# ProPrj_F080104_2024-08-08.net
KiCad netlist of a schematic drawn in EasyEDA Pro
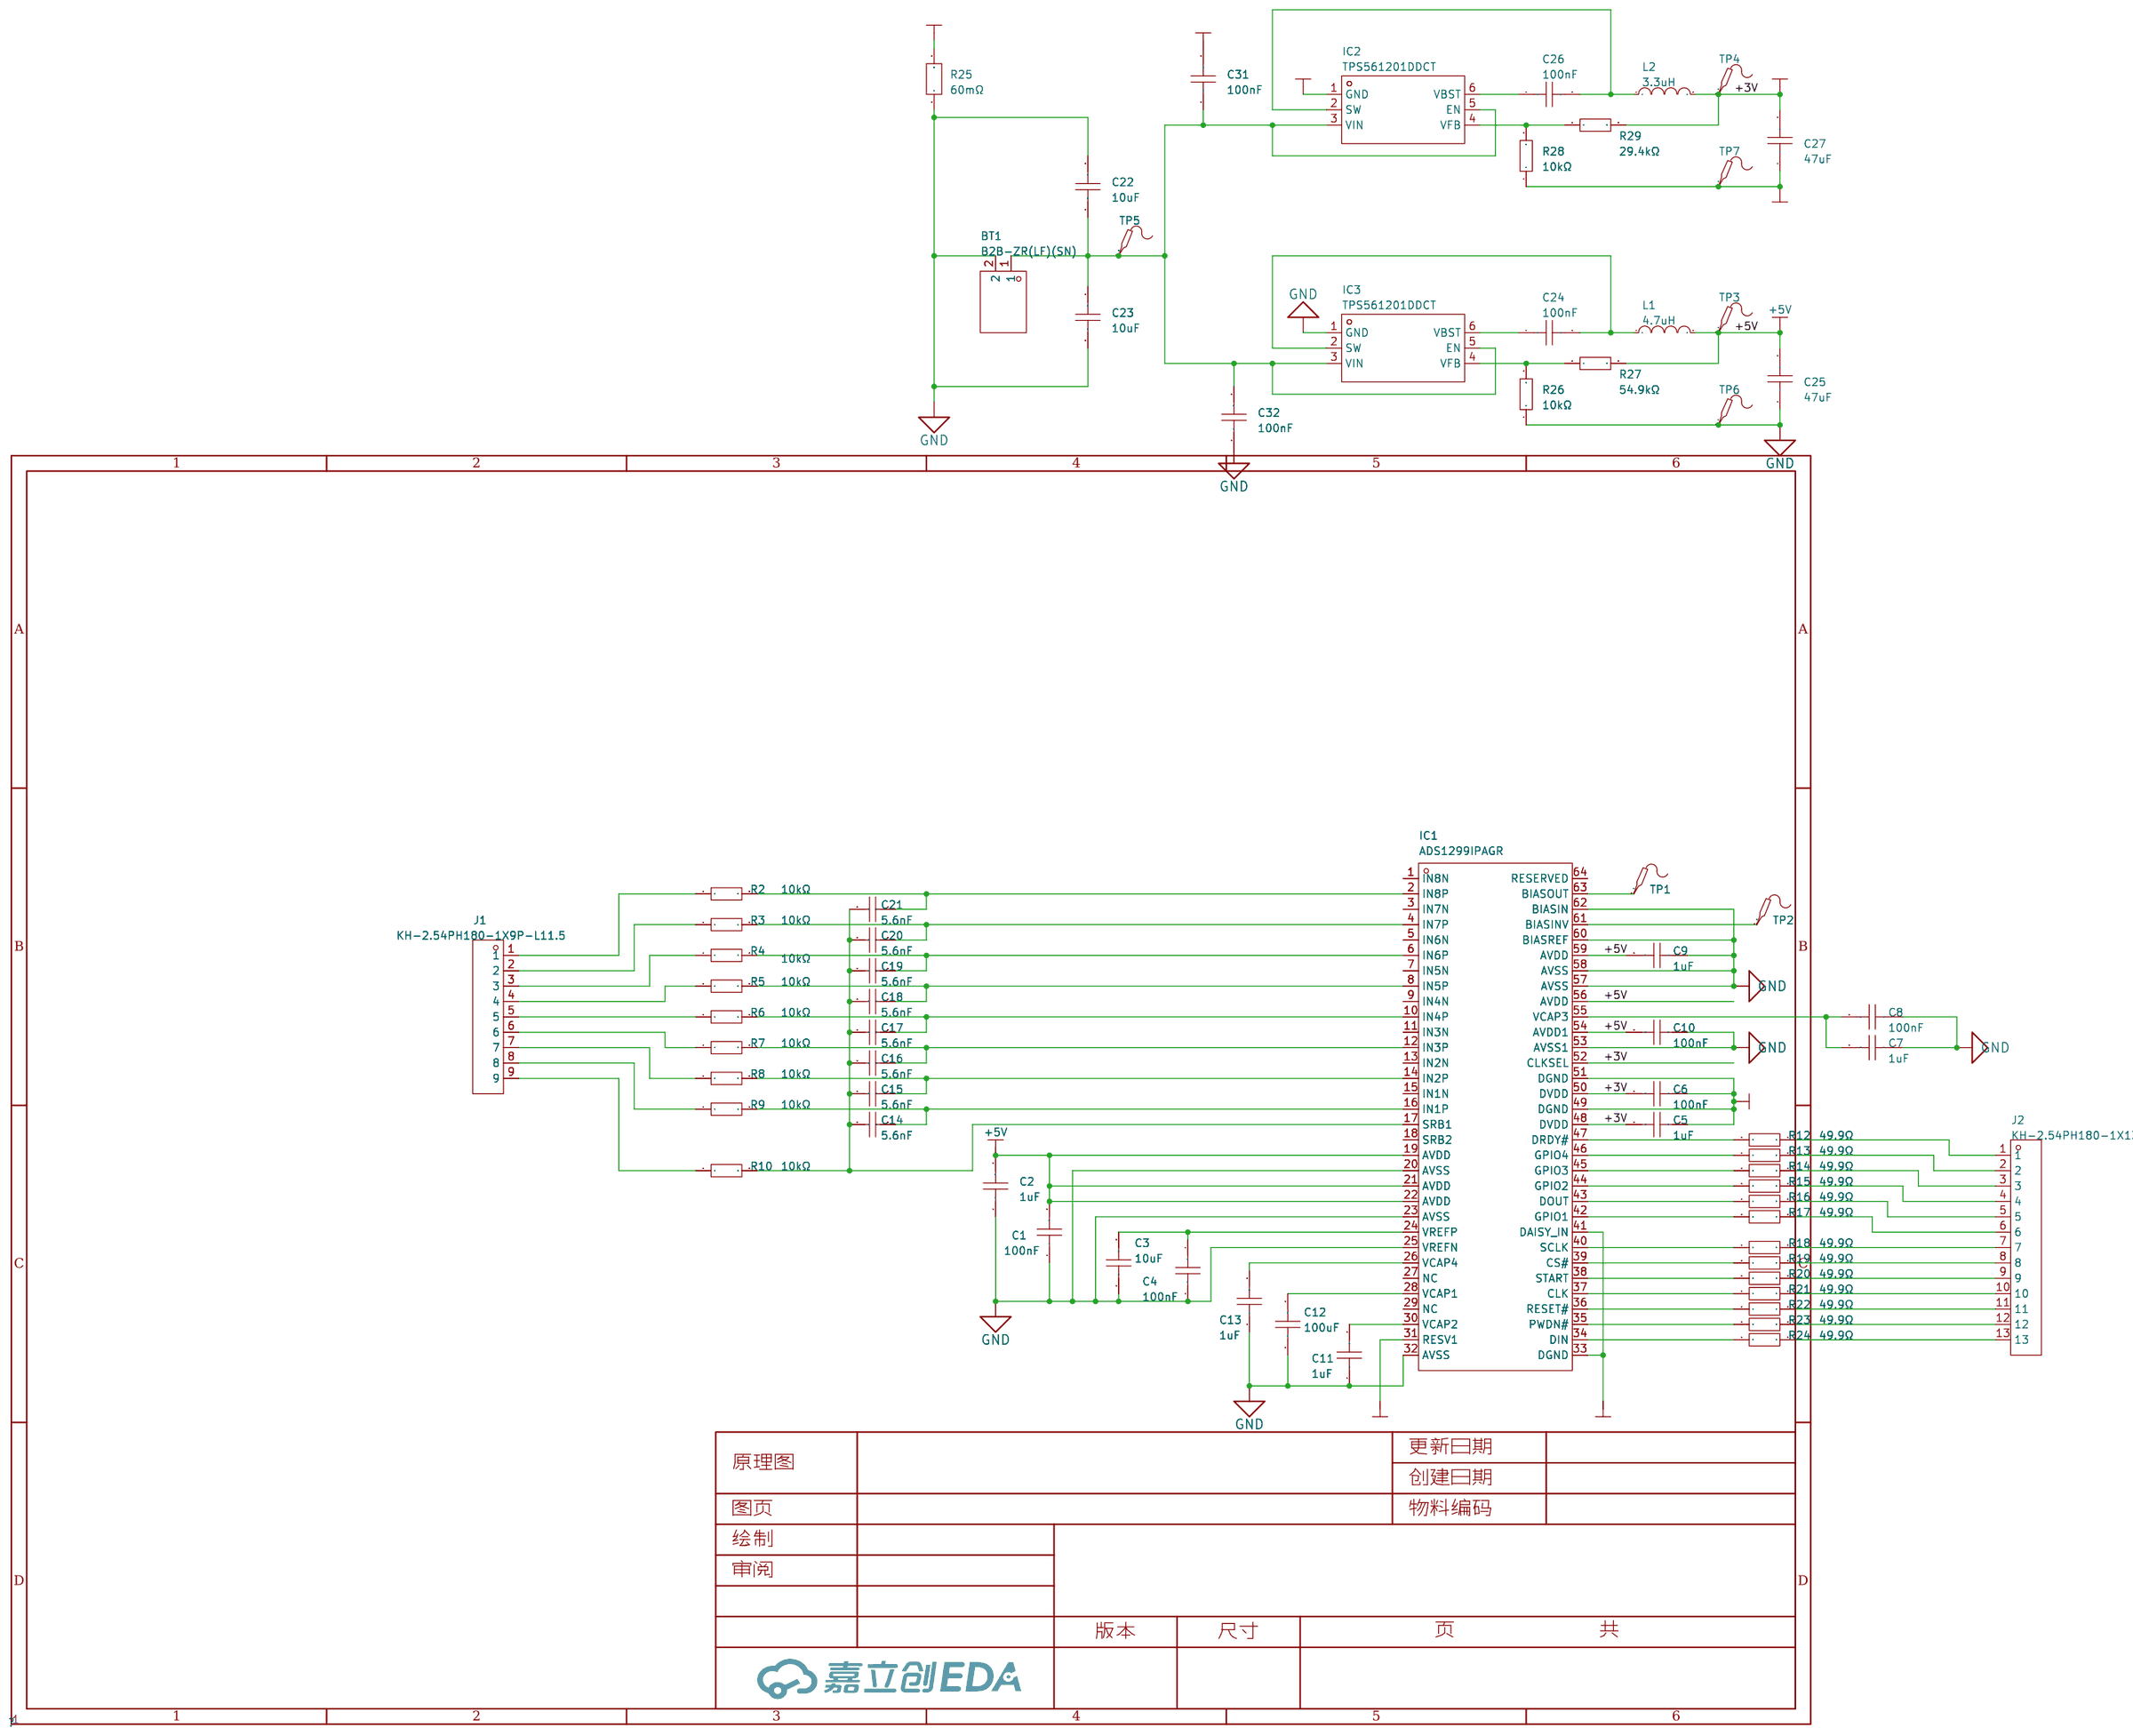
[diagram p0: schematic sheet]

(export (version "E")
  (design (tool "Eeschema 10.0.6"))
  (components
    (comp (ref "BT1")
      (value "B2B-ZR(LF)(SN)")
      (footprint "easyedapro:CONN-TH_B2B-ZR-LF-SN")
      (fields (field (name "Manufacturer") "JST"))
      (libsource (lib "easyedapro") (part "B2B-ZR (LF)(SN)"))
    )
    (comp (ref "C1")
      (value "100nF")
      (footprint "easyedapro:C0603")
      (description "容值:100nF;精度:±10%;额定电压:50V;材质(温度系数):X7R;")
      (fields
        (field (name "Manufacturer Part") "CC0603KRX7R9BB104")
        (field (name "Manufacturer") "YAGEO(国巨)")
      )
      (libsource (lib "easyedapro") (part "CC0603KRX7R9BB104"))
    )
    (comp (ref "C2")
      (value "1uF")
      (footprint "easyedapro:C0603")
      (description "容值:1uF;精度:±10%;额定电压:50V;材质(温度系数):X5R;")
      (fields
        (field (name "Manufacturer Part") "CL10A105KB8NNNC")
        (field (name "Manufacturer") "SAMSUNG(三星)")
      )
      (libsource (lib "easyedapro") (part "CL10A105KB8NNNC"))
    )
    (comp (ref "C3")
      (value "10uF")
      (footprint "easyedapro:C0805")
      (description "容值:10uF;精度:±10%;额定电压:25V;材质(温度系数):X5R;")
      (fields
        (field (name "Manufacturer Part") "CL21A106KAYNNNE")
        (field (name "Manufacturer") "SAMSUNG(三星)")
      )
      (libsource (lib "easyedapro") (part "CL21A106KAYNNNE"))
    )
    (comp (ref "C4")
      (value "100nF")
      (footprint "easyedapro:C0603")
      (description "容值:100nF;精度:±10%;额定电压:50V;材质(温度系数):X7R;")
      (fields
        (field (name "Manufacturer Part") "CC0603KRX7R9BB104")
        (field (name "Manufacturer") "YAGEO(国巨)")
      )
      (libsource (lib "easyedapro") (part "CC0603KRX7R9BB104"))
    )
    (comp (ref "C5")
      (value "1uF")
      (footprint "easyedapro:C0603")
      (description "容值:1uF;精度:±10%;额定电压:50V;材质(温度系数):X5R;")
      (fields
        (field (name "Manufacturer Part") "CL10A105KB8NNNC")
        (field (name "Manufacturer") "SAMSUNG(三星)")
      )
      (libsource (lib "easyedapro") (part "CL10A105KB8NNNC"))
    )
    (comp (ref "C6")
      (value "100nF")
      (footprint "easyedapro:C0603")
      (description "容值:100nF;精度:±10%;额定电压:50V;材质(温度系数):X7R;")
      (fields
        (field (name "Manufacturer Part") "CC0603KRX7R9BB104")
        (field (name "Manufacturer") "YAGEO(国巨)")
      )
      (libsource (lib "easyedapro") (part "CC0603KRX7R9BB104"))
    )
    (comp (ref "C7")
      (value "1uF")
      (footprint "easyedapro:C0603")
      (description "容值:1uF;精度:±10%;额定电压:50V;材质(温度系数):X5R;")
      (fields
        (field (name "Manufacturer Part") "CL10A105KB8NNNC")
        (field (name "Manufacturer") "SAMSUNG(三星)")
      )
      (libsource (lib "easyedapro") (part "CL10A105KB8NNNC"))
    )
    (comp (ref "C8")
      (value "100nF")
      (footprint "easyedapro:C0603")
      (description "容值:100nF;精度:±10%;额定电压:50V;材质(温度系数):X7R;")
      (fields
        (field (name "Manufacturer Part") "CC0603KRX7R9BB104")
        (field (name "Manufacturer") "YAGEO(国巨)")
      )
      (libsource (lib "easyedapro") (part "CC0603KRX7R9BB104"))
    )
    (comp (ref "C9")
      (value "1uF")
      (footprint "easyedapro:C0603")
      (description "容值:1uF;精度:±10%;额定电压:50V;材质(温度系数):X5R;")
      (fields
        (field (name "Manufacturer Part") "CL10A105KB8NNNC")
        (field (name "Manufacturer") "SAMSUNG(三星)")
      )
      (libsource (lib "easyedapro") (part "CL10A105KB8NNNC"))
    )
    (comp (ref "C10")
      (value "100nF")
      (footprint "easyedapro:C0603")
      (description "容值:100nF;精度:±10%;额定电压:50V;材质(温度系数):X7R;")
      (fields
        (field (name "Manufacturer Part") "CC0603KRX7R9BB104")
        (field (name "Manufacturer") "YAGEO(国巨)")
      )
      (libsource (lib "easyedapro") (part "CC0603KRX7R9BB104"))
    )
    (comp (ref "C11")
      (value "1uF")
      (footprint "easyedapro:C0603")
      (description "容值:1uF;精度:±10%;额定电压:50V;材质(温度系数):X5R;")
      (fields
        (field (name "Manufacturer Part") "CL10A105KB8NNNC")
        (field (name "Manufacturer") "SAMSUNG(三星)")
      )
      (libsource (lib "easyedapro") (part "CL10A105KB8NNNC"))
    )
    (comp (ref "C12")
      (value "100uF")
      (footprint "easyedapro:C1206")
      (description "容值:100uF;精度:±20%;额定电压:10V;材质(温度系数):X5R;")
      (fields
        (field (name "Manufacturer Part") "GRM31CR61A107ME05L")
        (field (name "Manufacturer") "muRata(村田)")
      )
      (libsource (lib "easyedapro") (part "GRM31CR61A107ME05L"))
    )
    (comp (ref "C13")
      (value "1uF")
      (footprint "easyedapro:C0603")
      (description "容值:1uF;精度:±10%;额定电压:50V;材质(温度系数):X5R;")
      (fields
        (field (name "Manufacturer Part") "CL10A105KB8NNNC")
        (field (name "Manufacturer") "SAMSUNG(三星)")
      )
      (libsource (lib "easyedapro") (part "CL10A105KB8NNNC"))
    )
    (comp (ref "C14")
      (value "5.6nF")
      (footprint "easyedapro:C0603")
      (description "容值:3.9nF;精度:±10%;额定电压:50V;材质(温度系数):X7R;")
      (fields
        (field (name "Manufacturer Part") "CC0603KRX7R9BB562")
        (field (name "Manufacturer") "YAGEO(国巨)")
      )
      (libsource (lib "easyedapro") (part "0603B392K500NT"))
    )
    (comp (ref "C15")
      (value "5.6nF")
      (footprint "easyedapro:C0603")
      (description "容值:3.9nF;精度:±10%;额定电压:50V;材质(温度系数):X7R;")
      (fields
        (field (name "Manufacturer Part") "CC0603KRX7R9BB562")
        (field (name "Manufacturer") "YAGEO(国巨)")
      )
      (libsource (lib "easyedapro") (part "0603B392K500NT"))
    )
    (comp (ref "C16")
      (value "5.6nF")
      (footprint "easyedapro:C0603")
      (description "容值:3.9nF;精度:±10%;额定电压:50V;材质(温度系数):X7R;")
      (fields
        (field (name "Manufacturer Part") "CC0603KRX7R9BB562")
        (field (name "Manufacturer") "YAGEO(国巨)")
      )
      (libsource (lib "easyedapro") (part "0603B392K500NT"))
    )
    (comp (ref "C17")
      (value "5.6nF")
      (footprint "easyedapro:C0603")
      (description "容值:3.9nF;精度:±10%;额定电压:50V;材质(温度系数):X7R;")
      (fields
        (field (name "Manufacturer Part") "CC0603KRX7R9BB562")
        (field (name "Manufacturer") "YAGEO(国巨)")
      )
      (libsource (lib "easyedapro") (part "0603B392K500NT"))
    )
    (comp (ref "C18")
      (value "5.6nF")
      (footprint "easyedapro:C0603")
      (description "容值:3.9nF;精度:±10%;额定电压:50V;材质(温度系数):X7R;")
      (fields
        (field (name "Manufacturer Part") "CC0603KRX7R9BB562")
        (field (name "Manufacturer") "YAGEO(国巨)")
      )
      (libsource (lib "easyedapro") (part "0603B392K500NT"))
    )
    (comp (ref "C19")
      (value "5.6nF")
      (footprint "easyedapro:C0603")
      (description "容值:3.9nF;精度:±10%;额定电压:50V;材质(温度系数):X7R;")
      (fields
        (field (name "Manufacturer Part") "CC0603KRX7R9BB562")
        (field (name "Manufacturer") "YAGEO(国巨)")
      )
      (libsource (lib "easyedapro") (part "0603B392K500NT"))
    )
    (comp (ref "C20")
      (value "5.6nF")
      (footprint "easyedapro:C0603")
      (description "容值:3.9nF;精度:±10%;额定电压:50V;材质(温度系数):X7R;")
      (fields
        (field (name "Manufacturer Part") "CC0603KRX7R9BB562")
        (field (name "Manufacturer") "YAGEO(国巨)")
      )
      (libsource (lib "easyedapro") (part "0603B392K500NT"))
    )
    (comp (ref "C21")
      (value "5.6nF")
      (footprint "easyedapro:C0603")
      (description "容值:3.9nF;精度:±10%;额定电压:50V;材质(温度系数):X7R;")
      (fields
        (field (name "Manufacturer Part") "CC0603KRX7R9BB562")
        (field (name "Manufacturer") "YAGEO(国巨)")
      )
      (libsource (lib "easyedapro") (part "0603B392K500NT"))
    )
    (comp (ref "C22")
      (value "10uF")
      (footprint "easyedapro:C0805")
      (description "容值:10uF;精度:±10%;额定电压:25V;材质(温度系数):X5R;")
      (fields
        (field (name "Manufacturer Part") "CL21A106KAYNNNE")
        (field (name "Manufacturer") "SAMSUNG(三星)")
      )
      (libsource (lib "easyedapro") (part "CL21A106KAYNNNE"))
    )
    (comp (ref "C23")
      (value "10uF")
      (footprint "easyedapro:C0805")
      (description "容值:10uF;精度:±10%;额定电压:25V;材质(温度系数):X5R;")
      (fields
        (field (name "Manufacturer Part") "CL21A106KAYNNNE")
        (field (name "Manufacturer") "SAMSUNG(三星)")
      )
      (libsource (lib "easyedapro") (part "CL21A106KAYNNNE"))
    )
    (comp (ref "C24")
      (value "100nF")
      (footprint "easyedapro:C0603")
      (description "容值:100nF;精度:±10%;额定电压:50V;材质(温度系数):X7R;")
      (fields
        (field (name "Manufacturer Part") "CC0603KRX7R9BB104")
        (field (name "Manufacturer") "YAGEO(国巨)")
      )
      (libsource (lib "easyedapro") (part "CC0603KRX7R9BB104"))
    )
    (comp (ref "C25")
      (value "47uF")
      (footprint "easyedapro:C0805")
      (description "容值:47uF;精度:±20%;额定电压:10V;材质(温度系数):X5R;")
      (fields
        (field (name "Manufacturer Part") "GRM21BR61A476ME15L")
        (field (name "Manufacturer") "muRata(村田)")
      )
      (libsource (lib "easyedapro") (part "GRM21BR61A476ME15L"))
    )
    (comp (ref "C26")
      (value "100nF")
      (footprint "easyedapro:C0603")
      (description "容值:100nF;精度:±10%;额定电压:50V;材质(温度系数):X7R;")
      (fields
        (field (name "Manufacturer Part") "CC0603KRX7R9BB104")
        (field (name "Manufacturer") "YAGEO(国巨)")
      )
      (libsource (lib "easyedapro") (part "CC0603KRX7R9BB104"))
    )
    (comp (ref "C27")
      (value "47uF")
      (footprint "easyedapro:C0805")
      (description "容值:47uF;精度:±20%;额定电压:10V;材质(温度系数):X5R;")
      (fields
        (field (name "Manufacturer Part") "GRM21BR61A476ME15L")
        (field (name "Manufacturer") "muRata(村田)")
      )
      (libsource (lib "easyedapro") (part "GRM21BR61A476ME15L"))
    )
    (comp (ref "C31")
      (value "100nF")
      (footprint "easyedapro:C0603")
      (description "容值:100nF;精度:±10%;额定电压:50V;材质(温度系数):X7R;")
      (fields
        (field (name "Manufacturer Part") "CC0603KRX7R9BB104")
        (field (name "Manufacturer") "YAGEO(国巨)")
      )
      (libsource (lib "easyedapro") (part "CC0603KRX7R9BB104"))
    )
    (comp (ref "C32")
      (value "100nF")
      (footprint "easyedapro:C0603")
      (description "容值:100nF;精度:±10%;额定电压:50V;材质(温度系数):X7R;")
      (fields
        (field (name "Manufacturer Part") "CC0603KRX7R9BB104")
        (field (name "Manufacturer") "YAGEO(国巨)")
      )
      (libsource (lib "easyedapro") (part "CC0603KRX7R9BB104"))
    )
    (comp (ref "IC1")
      (value "ADS1299IPAGR")
      (footprint "easyedapro:TQFP-64_L10.0-W10.0-P0.50-LS12.0-TL")
      (description "电源电压:5V；1.8V~3.6V;")
      (fields (field (name "Manufacturer") "TI(德州仪器)"))
      (libsource (lib "easyedapro") (part "ADS1299IPAGR"))
    )
    (comp (ref "IC2")
      (value "TPS561201DDCT")
      (footprint "easyedapro:SOT-23-6_L2.9-W1.6-P0.95-LS2.8-BR")
      (description "功能类型:降压型;输出类型:可调;输入电压:4.5V~17V;输出电压:760mV~7V;输出电流(最大值):1A;")
      (fields (field (name "Manufacturer") "TI(德州仪器)"))
      (libsource (lib "easyedapro") (part "TPS561201DDCT"))
    )
    (comp (ref "IC3")
      (value "TPS561201DDCT")
      (footprint "easyedapro:SOT-23-6_L2.9-W1.6-P0.95-LS2.8-BR")
      (description "功能类型:降压型;输出类型:可调;输入电压:4.5V~17V;输出电压:760mV~7V;输出电流(最大值):1A;")
      (fields (field (name "Manufacturer") "TI(德州仪器)"))
      (libsource (lib "easyedapro") (part "TPS561201DDCT"))
    )
    (comp (ref "J1")
      (value "KH-2.54PH180-1X9P-L11.5")
      (footprint "easyedapro:HDR-TH_9P-P2.54-V-M")
      (fields (field (name "Manufacturer") "kinghelm(金航标)"))
      (libsource (lib "easyedapro") (part "KH-2.54PH180-1X9P-L11.5"))
    )
    (comp (ref "J2")
      (value "KH-2.54PH180-1X13P-L11.5")
      (footprint "easyedapro:HDR-TH_13P-P2.54-V-M")
      (fields (field (name "Manufacturer") "kinghelm(金航标)"))
      (libsource (lib "easyedapro") (part "KH-2.54PH180-1X13P-L11.5"))
    )
    (comp (ref "L1")
      (value "4.7uH")
      (footprint "easyedapro:IND-SMD_L4.4-W4.2")
      (description "电感值:4.7uH;精度:±20%;额定电流:2.8A;饱和电流(Isat):3A;类型:一体成型电感;")
      (fields (field (name "Manufacturer Part") "FXL0420-4R7-M") (field (name "Manufacturer") "cjiang(长江微电)"))
      (libsource (lib "easyedapro") (part "FXL0420-4R7-M"))
    )
    (comp (ref "L2")
      (value "3.3uH")
      (footprint "easyedapro:IND-SMD_L4.4-W4.2-A")
      (description "电感值:3.3uH;精度:±20%;额定电流:3.3A;饱和电流(Isat):4A;类型:一体成型电感;")
      (fields (field (name "Manufacturer Part") "FXL0420-3R3-M") (field (name "Manufacturer") "cjiang(长江微电)"))
      (libsource (lib "easyedapro") (part "FXL0420-3R3-M"))
    )
    (comp (ref "R2")
      (value "10kΩ")
      (footprint "easyedapro:R0603")
      (description "电阻类型:厚膜电阻;阻值:10kΩ;精度:±1%;功率:100mW;最大工作电压:75V;温度系数:±100ppm/°C;")
      (fields
        (field (name "Manufacturer Part") "0603WAF1002T5E")
        (field (name "Manufacturer") "UNI-ROYAL(厚声)")
      )
      (libsource (lib "easyedapro") (part "0603WAF1002T5E"))
    )
    (comp (ref "R3")
      (value "10kΩ")
      (footprint "easyedapro:R0603")
      (description "电阻类型:厚膜电阻;阻值:10kΩ;精度:±1%;功率:100mW;最大工作电压:75V;温度系数:±100ppm/°C;")
      (fields
        (field (name "Manufacturer Part") "0603WAF1002T5E")
        (field (name "Manufacturer") "UNI-ROYAL(厚声)")
      )
      (libsource (lib "easyedapro") (part "0603WAF1002T5E"))
    )
    (comp (ref "R4")
      (value "10kΩ")
      (footprint "easyedapro:R0603")
      (description "电阻类型:厚膜电阻;阻值:10kΩ;精度:±1%;功率:100mW;最大工作电压:75V;温度系数:±100ppm/°C;")
      (fields
        (field (name "Manufacturer Part") "0603WAF1002T5E")
        (field (name "Manufacturer") "UNI-ROYAL(厚声)")
      )
      (libsource (lib "easyedapro") (part "0603WAF1002T5E"))
    )
    (comp (ref "R5")
      (value "10kΩ")
      (footprint "easyedapro:R0603")
      (description "电阻类型:厚膜电阻;阻值:10kΩ;精度:±1%;功率:100mW;最大工作电压:75V;温度系数:±100ppm/°C;")
      (fields
        (field (name "Manufacturer Part") "0603WAF1002T5E")
        (field (name "Manufacturer") "UNI-ROYAL(厚声)")
      )
      (libsource (lib "easyedapro") (part "0603WAF1002T5E"))
    )
    (comp (ref "R6")
      (value "10kΩ")
      (footprint "easyedapro:R0603")
      (description "电阻类型:厚膜电阻;阻值:10kΩ;精度:±1%;功率:100mW;最大工作电压:75V;温度系数:±100ppm/°C;")
      (fields
        (field (name "Manufacturer Part") "0603WAF1002T5E")
        (field (name "Manufacturer") "UNI-ROYAL(厚声)")
      )
      (libsource (lib "easyedapro") (part "0603WAF1002T5E"))
    )
    (comp (ref "R7")
      (value "10kΩ")
      (footprint "easyedapro:R0603")
      (description "电阻类型:厚膜电阻;阻值:10kΩ;精度:±1%;功率:100mW;最大工作电压:75V;温度系数:±100ppm/°C;")
      (fields
        (field (name "Manufacturer Part") "0603WAF1002T5E")
        (field (name "Manufacturer") "UNI-ROYAL(厚声)")
      )
      (libsource (lib "easyedapro") (part "0603WAF1002T5E"))
    )
    (comp (ref "R8")
      (value "10kΩ")
      (footprint "easyedapro:R0603")
      (description "电阻类型:厚膜电阻;阻值:10kΩ;精度:±1%;功率:100mW;最大工作电压:75V;温度系数:±100ppm/°C;")
      (fields
        (field (name "Manufacturer Part") "0603WAF1002T5E")
        (field (name "Manufacturer") "UNI-ROYAL(厚声)")
      )
      (libsource (lib "easyedapro") (part "0603WAF1002T5E"))
    )
    (comp (ref "R9")
      (value "10kΩ")
      (footprint "easyedapro:R0603")
      (description "电阻类型:厚膜电阻;阻值:10kΩ;精度:±1%;功率:100mW;最大工作电压:75V;温度系数:±100ppm/°C;")
      (fields
        (field (name "Manufacturer Part") "0603WAF1002T5E")
        (field (name "Manufacturer") "UNI-ROYAL(厚声)")
      )
      (libsource (lib "easyedapro") (part "0603WAF1002T5E"))
    )
    (comp (ref "R10")
      (value "10kΩ")
      (footprint "easyedapro:R0603")
      (description "电阻类型:厚膜电阻;阻值:10kΩ;精度:±1%;功率:100mW;最大工作电压:75V;温度系数:±100ppm/°C;")
      (fields
        (field (name "Manufacturer Part") "0603WAF1002T5E")
        (field (name "Manufacturer") "UNI-ROYAL(厚声)")
      )
      (libsource (lib "easyedapro") (part "0603WAF1002T5E"))
    )
    (comp (ref "R12")
      (value "49.9Ω")
      (footprint "easyedapro:R0603")
      (description "电阻类型:厚膜电阻;阻值:10kΩ;精度:±1%;功率:100mW;最大工作电压:75V;温度系数:±100ppm/°C;")
      (fields
        (field (name "Manufacturer Part") "0603WAF499JT5E")
        (field (name "Manufacturer") "UNI-ROYAL(厚声)")
      )
      (libsource (lib "easyedapro") (part "0603WAF1002T5E"))
    )
    (comp (ref "R13")
      (value "49.9Ω")
      (footprint "easyedapro:R0603")
      (description "电阻类型:厚膜电阻;阻值:10kΩ;精度:±1%;功率:100mW;最大工作电压:75V;温度系数:±100ppm/°C;")
      (fields
        (field (name "Manufacturer Part") "0603WAF499JT5E")
        (field (name "Manufacturer") "UNI-ROYAL(厚声)")
      )
      (libsource (lib "easyedapro") (part "0603WAF1002T5E"))
    )
    (comp (ref "R14")
      (value "49.9Ω")
      (footprint "easyedapro:R0603")
      (description "电阻类型:厚膜电阻;阻值:10kΩ;精度:±1%;功率:100mW;最大工作电压:75V;温度系数:±100ppm/°C;")
      (fields
        (field (name "Manufacturer Part") "0603WAF499JT5E")
        (field (name "Manufacturer") "UNI-ROYAL(厚声)")
      )
      (libsource (lib "easyedapro") (part "0603WAF1002T5E"))
    )
    (comp (ref "R15")
      (value "49.9Ω")
      (footprint "easyedapro:R0603")
      (description "电阻类型:厚膜电阻;阻值:10kΩ;精度:±1%;功率:100mW;最大工作电压:75V;温度系数:±100ppm/°C;")
      (fields
        (field (name "Manufacturer Part") "0603WAF499JT5E")
        (field (name "Manufacturer") "UNI-ROYAL(厚声)")
      )
      (libsource (lib "easyedapro") (part "0603WAF1002T5E"))
    )
    (comp (ref "R16")
      (value "49.9Ω")
      (footprint "easyedapro:R0603")
      (description "电阻类型:厚膜电阻;阻值:10kΩ;精度:±1%;功率:100mW;最大工作电压:75V;温度系数:±100ppm/°C;")
      (fields
        (field (name "Manufacturer Part") "0603WAF499JT5E")
        (field (name "Manufacturer") "UNI-ROYAL(厚声)")
      )
      (libsource (lib "easyedapro") (part "0603WAF1002T5E"))
    )
    (comp (ref "R17")
      (value "49.9Ω")
      (footprint "easyedapro:R0603")
      (description "电阻类型:厚膜电阻;阻值:10kΩ;精度:±1%;功率:100mW;最大工作电压:75V;温度系数:±100ppm/°C;")
      (fields
        (field (name "Manufacturer Part") "0603WAF499JT5E")
        (field (name "Manufacturer") "UNI-ROYAL(厚声)")
      )
      (libsource (lib "easyedapro") (part "0603WAF1002T5E"))
    )
    (comp (ref "R18")
      (value "49.9Ω")
      (footprint "easyedapro:R0603")
      (description "电阻类型:厚膜电阻;阻值:10kΩ;精度:±1%;功率:100mW;最大工作电压:75V;温度系数:±100ppm/°C;")
      (fields
        (field (name "Manufacturer Part") "0603WAF499JT5E")
        (field (name "Manufacturer") "UNI-ROYAL(厚声)")
      )
      (libsource (lib "easyedapro") (part "0603WAF1002T5E"))
    )
    (comp (ref "R19")
      (value "49.9Ω")
      (footprint "easyedapro:R0603")
      (description "电阻类型:厚膜电阻;阻值:10kΩ;精度:±1%;功率:100mW;最大工作电压:75V;温度系数:±100ppm/°C;")
      (fields
        (field (name "Manufacturer Part") "0603WAF499JT5E")
        (field (name "Manufacturer") "UNI-ROYAL(厚声)")
      )
      (libsource (lib "easyedapro") (part "0603WAF1002T5E"))
    )
    (comp (ref "R20")
      (value "49.9Ω")
      (footprint "easyedapro:R0603")
      (description "电阻类型:厚膜电阻;阻值:10kΩ;精度:±1%;功率:100mW;最大工作电压:75V;温度系数:±100ppm/°C;")
      (fields
        (field (name "Manufacturer Part") "0603WAF499JT5E")
        (field (name "Manufacturer") "UNI-ROYAL(厚声)")
      )
      (libsource (lib "easyedapro") (part "0603WAF1002T5E"))
    )
    (comp (ref "R21")
      (value "49.9Ω")
      (footprint "easyedapro:R0603")
      (description "电阻类型:厚膜电阻;阻值:10kΩ;精度:±1%;功率:100mW;最大工作电压:75V;温度系数:±100ppm/°C;")
      (fields
        (field (name "Manufacturer Part") "0603WAF499JT5E")
        (field (name "Manufacturer") "UNI-ROYAL(厚声)")
      )
      (libsource (lib "easyedapro") (part "0603WAF1002T5E"))
    )
    (comp (ref "R22")
      (value "49.9Ω")
      (footprint "easyedapro:R0603")
      (description "电阻类型:厚膜电阻;阻值:10kΩ;精度:±1%;功率:100mW;最大工作电压:75V;温度系数:±100ppm/°C;")
      (fields
        (field (name "Manufacturer Part") "0603WAF499JT5E")
        (field (name "Manufacturer") "UNI-ROYAL(厚声)")
      )
      (libsource (lib "easyedapro") (part "0603WAF1002T5E"))
    )
    (comp (ref "R23")
      (value "49.9Ω")
      (footprint "easyedapro:R0603")
      (description "电阻类型:厚膜电阻;阻值:10kΩ;精度:±1%;功率:100mW;最大工作电压:75V;温度系数:±100ppm/°C;")
      (fields
        (field (name "Manufacturer Part") "0603WAF499JT5E")
        (field (name "Manufacturer") "UNI-ROYAL(厚声)")
      )
      (libsource (lib "easyedapro") (part "0603WAF1002T5E"))
    )
    (comp (ref "R24")
      (value "49.9Ω")
      (footprint "easyedapro:R0603")
      (description "电阻类型:厚膜电阻;阻值:10kΩ;精度:±1%;功率:100mW;最大工作电压:75V;温度系数:±100ppm/°C;")
      (fields
        (field (name "Manufacturer Part") "0603WAF499JT5E")
        (field (name "Manufacturer") "UNI-ROYAL(厚声)")
      )
      (libsource (lib "easyedapro") (part "0603WAF1002T5E"))
    )
    (comp (ref "R25")
      (value "60mΩ")
      (footprint "easyedapro:R2512")
      (description "电阻类型:厚膜电阻;阻值:60mΩ;精度:±1%;功率:1W;最大工作电压:200V;温度系数:±800ppm/°C;")
      (fields
        (field (name "Manufacturer Part") "25121WF600MT4E")
        (field (name "Manufacturer") "UNI-ROYAL(厚声)")
      )
      (libsource (lib "easyedapro") (part "25121WF600MT4E"))
    )
    (comp (ref "R26")
      (value "10kΩ")
      (footprint "easyedapro:R0603")
      (description "电阻类型:厚膜电阻;阻值:10kΩ;精度:±1%;功率:100mW;最大工作电压:75V;温度系数:±100ppm/°C;")
      (fields
        (field (name "Manufacturer Part") "0603WAF1002T5E")
        (field (name "Manufacturer") "UNI-ROYAL(厚声)")
      )
      (libsource (lib "easyedapro") (part "0603WAF1002T5E"))
    )
    (comp (ref "R27")
      (value "54.9kΩ")
      (footprint "easyedapro:R0603")
      (description "电阻类型:厚膜电阻;阻值:54.9kΩ;精度:±1%;功率:100mW;最大工作电压:75V;温度系数:±100ppm/°C;")
      (fields
        (field (name "Manufacturer Part") "0603WAF5492T5E")
        (field (name "Manufacturer") "UNI-ROYAL(厚声)")
      )
      (libsource (lib "easyedapro") (part "0603WAF5492T5E"))
    )
    (comp (ref "R28")
      (value "10kΩ")
      (footprint "easyedapro:R0603")
      (description "电阻类型:厚膜电阻;阻值:10kΩ;精度:±1%;功率:100mW;最大工作电压:75V;温度系数:±100ppm/°C;")
      (fields
        (field (name "Manufacturer Part") "0603WAF1002T5E")
        (field (name "Manufacturer") "UNI-ROYAL(厚声)")
      )
      (libsource (lib "easyedapro") (part "0603WAF1002T5E"))
    )
    (comp (ref "R29")
      (value "29.4kΩ")
      (footprint "easyedapro:R0603")
      (description "电阻类型:厚膜电阻;阻值:29.4kΩ;精度:±1%;功率:100mW;最大工作电压:75V;温度系数:±100ppm/°C;")
      (fields
        (field (name "Manufacturer Part") "0603WAF2942T5E")
        (field (name "Manufacturer") "UNI-ROYAL(厚声)")
      )
      (libsource (lib "easyedapro") (part "0603WAF2942T5E"))
    )
    (comp (ref "TP1")
      (value "~")
      (footprint "easyedapro:Test-Point-0.5mm")
      (description "Test Point 测试点")
      (libsource (lib "easyedapro") (part "Test-Point"))
    )
    (comp (ref "TP2")
      (value "~")
      (footprint "easyedapro:Test-Point-0.5mm")
      (description "Test Point 测试点")
      (libsource (lib "easyedapro") (part "Test-Point"))
    )
    (comp (ref "TP3")
      (value "~")
      (footprint "easyedapro:Test-Point-0.5mm")
      (description "Test Point 测试点")
      (libsource (lib "easyedapro") (part "Test-Point"))
    )
    (comp (ref "TP4")
      (value "~")
      (footprint "easyedapro:Test-Point-0.5mm")
      (description "Test Point 测试点")
      (libsource (lib "easyedapro") (part "Test-Point"))
    )
    (comp (ref "TP5")
      (value "~")
      (footprint "easyedapro:Test-Point-0.5mm")
      (description "Test Point 测试点")
      (libsource (lib "easyedapro") (part "Test-Point"))
    )
    (comp (ref "TP6")
      (value "~")
      (footprint "easyedapro:Test-Point-0.5mm")
      (description "Test Point 测试点")
      (libsource (lib "easyedapro") (part "Test-Point"))
    )
    (comp (ref "TP7")
      (value "~")
      (footprint "easyedapro:Test-Point-0.5mm")
      (description "Test Point 测试点")
      (libsource (lib "easyedapro") (part "Test-Point"))
    )
  )
  (nets
    (net (code "1") (name "+3V") (class "Default")
      (node (ref "C27") (pin "2") (pinfunction "2_2") (pintype "input"))
      (node (ref "C5") (pin "2") (pinfunction "2_2") (pintype "unspecified"))
      (node (ref "C6") (pin "2") (pinfunction "2_2") (pintype "unspecified"))
      (node (ref "IC1") (pin "48") (pinfunction "DVDD_48") (pintype "unspecified"))
      (node (ref "IC1") (pin "50") (pinfunction "DVDD_50") (pintype "unspecified"))
      (node (ref "IC1") (pin "52") (pinfunction "CLKSEL_52") (pintype "unspecified"))
      (node (ref "L2") (pin "2") (pinfunction "2_2") (pintype "unspecified"))
      (node (ref "R29") (pin "2") (pinfunction "2_2") (pintype "input"))
      (node (ref "TP4") (pin "1") (pinfunction "1_1") (pintype "input"))
    )
    (net (code "2") (name "+5V") (class "Default")
      (node (ref "C1") (pin "2") (pinfunction "2_2") (pintype "unspecified"))
      (node (ref "C10") (pin "2") (pinfunction "2_2") (pintype "unspecified"))
      (node (ref "C2") (pin "2") (pinfunction "2_2") (pintype "unspecified"))
      (node (ref "C25") (pin "2") (pinfunction "2_2") (pintype "input"))
      (node (ref "C9") (pin "2") (pinfunction "2_2") (pintype "unspecified"))
      (node (ref "IC1") (pin "19") (pinfunction "AVDD_19") (pintype "unspecified"))
      (node (ref "IC1") (pin "21") (pinfunction "AVDD_21") (pintype "unspecified"))
      (node (ref "IC1") (pin "22") (pinfunction "AVDD_22") (pintype "unspecified"))
      (node (ref "IC1") (pin "54") (pinfunction "AVDD1_54") (pintype "unspecified"))
      (node (ref "IC1") (pin "56") (pinfunction "AVDD_56") (pintype "unspecified"))
      (node (ref "IC1") (pin "59") (pinfunction "AVDD_59") (pintype "unspecified"))
      (node (ref "L1") (pin "2") (pinfunction "2_2") (pintype "unspecified"))
      (node (ref "R27") (pin "2") (pinfunction "2_2") (pintype "input"))
      (node (ref "TP3") (pin "1") (pinfunction "1_1") (pintype "input"))
    )
    (net (code "3") (name "GND") (class "Default")
      (node (ref "BT1") (pin "2") (pinfunction "2_2") (pintype "unspecified"))
      (node (ref "C1") (pin "1") (pinfunction "1_1") (pintype "unspecified"))
      (node (ref "C10") (pin "1") (pinfunction "1_1") (pintype "unspecified"))
      (node (ref "C11") (pin "1") (pinfunction "1_1") (pintype "unspecified"))
      (node (ref "C12") (pin "2") (pinfunction "2_2") (pintype "unspecified"))
      (node (ref "C13") (pin "1") (pinfunction "1_1") (pintype "unspecified"))
      (node (ref "C2") (pin "1") (pinfunction "1_1") (pintype "unspecified"))
      (node (ref "C22") (pin "2") (pinfunction "2_2") (pintype "unspecified"))
      (node (ref "C23") (pin "2") (pinfunction "2_2") (pintype "unspecified"))
      (node (ref "C25") (pin "1") (pinfunction "1_1") (pintype "input"))
      (node (ref "C3") (pin "1") (pinfunction "1_1") (pintype "unspecified"))
      (node (ref "C32") (pin "1") (pinfunction "1_1") (pintype "unspecified"))
      (node (ref "C4") (pin "2") (pinfunction "2_2") (pintype "unspecified"))
      (node (ref "C7") (pin "1") (pinfunction "1_1") (pintype "unspecified"))
      (node (ref "C8") (pin "1") (pinfunction "1_1") (pintype "unspecified"))
      (node (ref "C9") (pin "1") (pinfunction "1_1") (pintype "unspecified"))
      (node (ref "IC1") (pin "20") (pinfunction "AVSS_20") (pintype "unspecified"))
      (node (ref "IC1") (pin "23") (pinfunction "AVSS_23") (pintype "unspecified"))
      (node (ref "IC1") (pin "25") (pinfunction "VREFN_25") (pintype "unspecified"))
      (node (ref "IC1") (pin "32") (pinfunction "AVSS_32") (pintype "unspecified"))
      (node (ref "IC1") (pin "53") (pinfunction "AVSS1_53") (pintype "unspecified"))
      (node (ref "IC1") (pin "57") (pinfunction "AVSS_57") (pintype "unspecified"))
      (node (ref "IC1") (pin "58") (pinfunction "AVSS_58") (pintype "unspecified"))
      (node (ref "IC1") (pin "60") (pinfunction "BIASREF_60") (pintype "unspecified"))
      (node (ref "IC1") (pin "62") (pinfunction "BIASIN_62") (pintype "unspecified"))
      (node (ref "IC3") (pin "1") (pinfunction "GND_1") (pintype "input"))
      (node (ref "R25") (pin "1") (pinfunction "1_1") (pintype "unspecified"))
      (node (ref "R26") (pin "1") (pinfunction "1_1") (pintype "input"))
      (node (ref "TP6") (pin "1") (pinfunction "1_1") (pintype "input"))
    )
    (net (code "4") (name "GNDD") (class "Default")
      (node (ref "C27") (pin "1") (pinfunction "1_1") (pintype "input"))
      (node (ref "C31") (pin "2") (pinfunction "2_2") (pintype "unspecified"))
      (node (ref "C5") (pin "1") (pinfunction "1_1") (pintype "unspecified"))
      (node (ref "C6") (pin "1") (pinfunction "1_1") (pintype "unspecified"))
      (node (ref "IC1") (pin "31") (pinfunction "RESV1_31") (pintype "unspecified"))
      (node (ref "IC1") (pin "33") (pinfunction "DGND_33") (pintype "unspecified"))
      (node (ref "IC1") (pin "41") (pinfunction "DAISY_IN_41") (pintype "unspecified"))
      (node (ref "IC1") (pin "49") (pinfunction "DGND_49") (pintype "unspecified"))
      (node (ref "IC1") (pin "51") (pinfunction "DGND_51") (pintype "unspecified"))
      (node (ref "IC2") (pin "1") (pinfunction "GND_1") (pintype "input"))
      (node (ref "R25") (pin "2") (pinfunction "2_2") (pintype "unspecified"))
      (node (ref "R28") (pin "1") (pinfunction "1_1") (pintype "input"))
      (node (ref "TP7") (pin "1") (pinfunction "1_1") (pintype "input"))
    )
    (net (code "5") (name "Net-(IC1-BIASINV)") (class "Default")
      (node (ref "IC1") (pin "61") (pinfunction "BIASINV_61") (pintype "unspecified"))
      (node (ref "TP2") (pin "1") (pinfunction "1_1") (pintype "input"))
    )
    (net (code "6") (name "Net-(IC1-BIASOUT)") (class "Default")
      (node (ref "IC1") (pin "63") (pinfunction "BIASOUT_63") (pintype "unspecified"))
      (node (ref "TP1") (pin "1") (pinfunction "1_1") (pintype "input"))
    )
    (net (code "7") (name "Net-(IC1-CLK)") (class "Default")
      (node (ref "IC1") (pin "37") (pinfunction "CLK_37") (pintype "unspecified"))
      (node (ref "R21") (pin "1") (pinfunction "1_1") (pintype "input"))
    )
    (net (code "8") (name "Net-(IC1-CS#)") (class "Default")
      (node (ref "IC1") (pin "39") (pinfunction "CS#_39") (pintype "unspecified"))
      (node (ref "R19") (pin "1") (pinfunction "1_1") (pintype "input"))
    )
    (net (code "9") (name "Net-(IC1-DIN)") (class "Default")
      (node (ref "IC1") (pin "34") (pinfunction "DIN_34") (pintype "unspecified"))
      (node (ref "R24") (pin "1") (pinfunction "1_1") (pintype "input"))
    )
    (net (code "10") (name "Net-(IC1-DOUT)") (class "Default")
      (node (ref "IC1") (pin "43") (pinfunction "DOUT_43") (pintype "unspecified"))
      (node (ref "R16") (pin "1") (pinfunction "1_1") (pintype "input"))
    )
    (net (code "11") (name "Net-(IC1-DRDY#)") (class "Default")
      (node (ref "IC1") (pin "47") (pinfunction "DRDY#_47") (pintype "unspecified"))
      (node (ref "R12") (pin "1") (pinfunction "1_1") (pintype "input"))
    )
    (net (code "12") (name "Net-(IC1-GPIO1)") (class "Default")
      (node (ref "IC1") (pin "42") (pinfunction "GPIO1_42") (pintype "unspecified"))
      (node (ref "R17") (pin "1") (pinfunction "1_1") (pintype "input"))
    )
    (net (code "13") (name "Net-(IC1-GPIO2)") (class "Default")
      (node (ref "IC1") (pin "44") (pinfunction "GPIO2_44") (pintype "unspecified"))
      (node (ref "R15") (pin "1") (pinfunction "1_1") (pintype "input"))
    )
    (net (code "14") (name "Net-(IC1-GPIO3)") (class "Default")
      (node (ref "IC1") (pin "45") (pinfunction "GPIO3_45") (pintype "unspecified"))
      (node (ref "R14") (pin "1") (pinfunction "1_1") (pintype "input"))
    )
    (net (code "15") (name "Net-(IC1-GPIO4)") (class "Default")
      (node (ref "IC1") (pin "46") (pinfunction "GPIO4_46") (pintype "unspecified"))
      (node (ref "R13") (pin "1") (pinfunction "1_1") (pintype "input"))
    )
    (net (code "16") (name "Net-(IC1-IN1P)") (class "Default")
      (node (ref "C14") (pin "1") (pinfunction "1_1") (pintype "input"))
      (node (ref "IC1") (pin "16") (pinfunction "IN1P_16") (pintype "unspecified"))
      (node (ref "R9") (pin "2") (pinfunction "2_2") (pintype "input"))
    )
    (net (code "17") (name "Net-(IC1-IN2P)") (class "Default")
      (node (ref "C15") (pin "1") (pinfunction "1_1") (pintype "input"))
      (node (ref "IC1") (pin "14") (pinfunction "IN2P_14") (pintype "unspecified"))
      (node (ref "R8") (pin "2") (pinfunction "2_2") (pintype "input"))
    )
    (net (code "18") (name "Net-(IC1-IN3P)") (class "Default")
      (node (ref "C16") (pin "1") (pinfunction "1_1") (pintype "input"))
      (node (ref "IC1") (pin "12") (pinfunction "IN3P_12") (pintype "unspecified"))
      (node (ref "R7") (pin "2") (pinfunction "2_2") (pintype "input"))
    )
    (net (code "19") (name "Net-(IC1-IN4P)") (class "Default")
      (node (ref "C17") (pin "1") (pinfunction "1_1") (pintype "input"))
      (node (ref "IC1") (pin "10") (pinfunction "IN4P_10") (pintype "unspecified"))
      (node (ref "R6") (pin "2") (pinfunction "2_2") (pintype "input"))
    )
    (net (code "20") (name "Net-(IC1-IN5P)") (class "Default")
      (node (ref "C18") (pin "1") (pinfunction "1_1") (pintype "input"))
      (node (ref "IC1") (pin "8") (pinfunction "IN5P_8") (pintype "unspecified"))
      (node (ref "R5") (pin "2") (pinfunction "2_2") (pintype "input"))
    )
    (net (code "21") (name "Net-(IC1-IN6P)") (class "Default")
      (node (ref "C19") (pin "1") (pinfunction "1_1") (pintype "input"))
      (node (ref "IC1") (pin "6") (pinfunction "IN6P_6") (pintype "unspecified"))
      (node (ref "R4") (pin "2") (pinfunction "2_2") (pintype "input"))
    )
    (net (code "22") (name "Net-(IC1-IN7P)") (class "Default")
      (node (ref "C20") (pin "1") (pinfunction "1_1") (pintype "input"))
      (node (ref "IC1") (pin "4") (pinfunction "IN7P_4") (pintype "unspecified"))
      (node (ref "R3") (pin "2") (pinfunction "2_2") (pintype "input"))
    )
    (net (code "23") (name "Net-(IC1-IN8P)") (class "Default")
      (node (ref "C21") (pin "1") (pinfunction "1_1") (pintype "input"))
      (node (ref "IC1") (pin "2") (pinfunction "IN8P_2") (pintype "unspecified"))
      (node (ref "R2") (pin "2") (pinfunction "2_2") (pintype "input"))
    )
    (net (code "24") (name "Net-(IC1-PWDN#)") (class "Default")
      (node (ref "IC1") (pin "35") (pinfunction "PWDN#_35") (pintype "unspecified"))
      (node (ref "R23") (pin "1") (pinfunction "1_1") (pintype "input"))
    )
    (net (code "25") (name "Net-(IC1-RESET#)") (class "Default")
      (node (ref "IC1") (pin "36") (pinfunction "RESET#_36") (pintype "unspecified"))
      (node (ref "R22") (pin "1") (pinfunction "1_1") (pintype "input"))
    )
    (net (code "26") (name "Net-(IC1-SCLK)") (class "Default")
      (node (ref "IC1") (pin "40") (pinfunction "SCLK_40") (pintype "unspecified"))
      (node (ref "R18") (pin "1") (pinfunction "1_1") (pintype "input"))
    )
    (net (code "27") (name "Net-(IC1-SRB1)") (class "Default")
      (node (ref "C14") (pin "2") (pinfunction "2_2") (pintype "input"))
      (node (ref "C15") (pin "2") (pinfunction "2_2") (pintype "input"))
      (node (ref "C16") (pin "2") (pinfunction "2_2") (pintype "input"))
      (node (ref "C17") (pin "2") (pinfunction "2_2") (pintype "input"))
      (node (ref "C18") (pin "2") (pinfunction "2_2") (pintype "input"))
      (node (ref "C19") (pin "2") (pinfunction "2_2") (pintype "input"))
      (node (ref "C20") (pin "2") (pinfunction "2_2") (pintype "input"))
      (node (ref "C21") (pin "2") (pinfunction "2_2") (pintype "input"))
      (node (ref "IC1") (pin "17") (pinfunction "SRB1_17") (pintype "unspecified"))
      (node (ref "R10") (pin "2") (pinfunction "2_2") (pintype "input"))
    )
    (net (code "28") (name "Net-(IC1-START)") (class "Default")
      (node (ref "IC1") (pin "38") (pinfunction "START_38") (pintype "unspecified"))
      (node (ref "R20") (pin "1") (pinfunction "1_1") (pintype "input"))
    )
    (net (code "29") (name "Net-(IC1-VCAP1)") (class "Default")
      (node (ref "C12") (pin "1") (pinfunction "1_1") (pintype "unspecified"))
      (node (ref "IC1") (pin "28") (pinfunction "VCAP1_28") (pintype "unspecified"))
    )
    (net (code "30") (name "Net-(IC1-VCAP2)") (class "Default")
      (node (ref "C11") (pin "2") (pinfunction "2_2") (pintype "unspecified"))
      (node (ref "IC1") (pin "30") (pinfunction "VCAP2_30") (pintype "unspecified"))
    )
    (net (code "31") (name "Net-(IC1-VCAP3)") (class "Default")
      (node (ref "C7") (pin "2") (pinfunction "2_2") (pintype "unspecified"))
      (node (ref "C8") (pin "2") (pinfunction "2_2") (pintype "unspecified"))
      (node (ref "IC1") (pin "55") (pinfunction "VCAP3_55") (pintype "unspecified"))
    )
    (net (code "32") (name "Net-(IC1-VCAP4)") (class "Default")
      (node (ref "C13") (pin "2") (pinfunction "2_2") (pintype "unspecified"))
      (node (ref "IC1") (pin "26") (pinfunction "VCAP4_26") (pintype "unspecified"))
    )
    (net (code "33") (name "Net-(IC1-VREFP)") (class "Default")
      (node (ref "C3") (pin "2") (pinfunction "2_2") (pintype "unspecified"))
      (node (ref "C4") (pin "1") (pinfunction "1_1") (pintype "unspecified"))
      (node (ref "IC1") (pin "24") (pinfunction "VREFP_24") (pintype "unspecified"))
    )
    (net (code "34") (name "Net-(IC2-EN)") (class "Default")
      (node (ref "BT1") (pin "1") (pinfunction "1_1") (pintype "unspecified"))
      (node (ref "C22") (pin "1") (pinfunction "1_1") (pintype "unspecified"))
      (node (ref "C23") (pin "1") (pinfunction "1_1") (pintype "unspecified"))
      (node (ref "C31") (pin "1") (pinfunction "1_1") (pintype "unspecified"))
      (node (ref "C32") (pin "2") (pinfunction "2_2") (pintype "unspecified"))
      (node (ref "IC2") (pin "3") (pinfunction "VIN_3") (pintype "input"))
      (node (ref "IC2") (pin "5") (pinfunction "EN_5") (pintype "input"))
      (node (ref "IC3") (pin "3") (pinfunction "VIN_3") (pintype "input"))
      (node (ref "IC3") (pin "5") (pinfunction "EN_5") (pintype "input"))
      (node (ref "TP5") (pin "1") (pinfunction "1_1") (pintype "input"))
    )
    (net (code "35") (name "Net-(IC2-SW)") (class "Default")
      (node (ref "C26") (pin "2") (pinfunction "2_2") (pintype "unspecified"))
      (node (ref "IC2") (pin "2") (pinfunction "SW_2") (pintype "input"))
      (node (ref "L2") (pin "1") (pinfunction "1_1") (pintype "unspecified"))
    )
    (net (code "36") (name "Net-(IC2-VBST)") (class "Default")
      (node (ref "C26") (pin "1") (pinfunction "1_1") (pintype "unspecified"))
      (node (ref "IC2") (pin "6") (pinfunction "VBST_6") (pintype "input"))
    )
    (net (code "37") (name "Net-(IC2-VFB)") (class "Default")
      (node (ref "IC2") (pin "4") (pinfunction "VFB_4") (pintype "input"))
      (node (ref "R28") (pin "2") (pinfunction "2_2") (pintype "input"))
      (node (ref "R29") (pin "1") (pinfunction "1_1") (pintype "input"))
    )
    (net (code "38") (name "Net-(IC3-SW)") (class "Default")
      (node (ref "C24") (pin "2") (pinfunction "2_2") (pintype "unspecified"))
      (node (ref "IC3") (pin "2") (pinfunction "SW_2") (pintype "input"))
      (node (ref "L1") (pin "1") (pinfunction "1_1") (pintype "unspecified"))
    )
    (net (code "39") (name "Net-(IC3-VBST)") (class "Default")
      (node (ref "C24") (pin "1") (pinfunction "1_1") (pintype "unspecified"))
      (node (ref "IC3") (pin "6") (pinfunction "VBST_6") (pintype "input"))
    )
    (net (code "40") (name "Net-(IC3-VFB)") (class "Default")
      (node (ref "IC3") (pin "4") (pinfunction "VFB_4") (pintype "input"))
      (node (ref "R26") (pin "2") (pinfunction "2_2") (pintype "input"))
      (node (ref "R27") (pin "1") (pinfunction "1_1") (pintype "input"))
    )
    (net (code "41") (name "Net-(J1-Pad1)") (class "Default")
      (node (ref "J1") (pin "1") (pinfunction "1_1") (pintype "unspecified"))
      (node (ref "R2") (pin "1") (pinfunction "1_1") (pintype "input"))
    )
    (net (code "42") (name "Net-(J1-Pad2)") (class "Default")
      (node (ref "J1") (pin "2") (pinfunction "2_2") (pintype "unspecified"))
      (node (ref "R3") (pin "1") (pinfunction "1_1") (pintype "input"))
    )
    (net (code "43") (name "Net-(J1-Pad3)") (class "Default")
      (node (ref "J1") (pin "3") (pinfunction "3_3") (pintype "unspecified"))
      (node (ref "R4") (pin "1") (pinfunction "1_1") (pintype "input"))
    )
    (net (code "44") (name "Net-(J1-Pad4)") (class "Default")
      (node (ref "J1") (pin "4") (pinfunction "4_4") (pintype "unspecified"))
      (node (ref "R5") (pin "1") (pinfunction "1_1") (pintype "input"))
    )
    (net (code "45") (name "Net-(J1-Pad5)") (class "Default")
      (node (ref "J1") (pin "5") (pinfunction "5_5") (pintype "unspecified"))
      (node (ref "R6") (pin "1") (pinfunction "1_1") (pintype "input"))
    )
    (net (code "46") (name "Net-(J1-Pad6)") (class "Default")
      (node (ref "J1") (pin "6") (pinfunction "6_6") (pintype "unspecified"))
      (node (ref "R7") (pin "1") (pinfunction "1_1") (pintype "input"))
    )
    (net (code "47") (name "Net-(J1-Pad7)") (class "Default")
      (node (ref "J1") (pin "7") (pinfunction "7_7") (pintype "unspecified"))
      (node (ref "R8") (pin "1") (pinfunction "1_1") (pintype "input"))
    )
    (net (code "48") (name "Net-(J1-Pad8)") (class "Default")
      (node (ref "J1") (pin "8") (pinfunction "8_8") (pintype "unspecified"))
      (node (ref "R9") (pin "1") (pinfunction "1_1") (pintype "input"))
    )
    (net (code "49") (name "Net-(J1-Pad9)") (class "Default")
      (node (ref "J1") (pin "9") (pinfunction "9_9") (pintype "unspecified"))
      (node (ref "R10") (pin "1") (pinfunction "1_1") (pintype "input"))
    )
    (net (code "50") (name "Net-(J2-Pad1)") (class "Default")
      (node (ref "J2") (pin "1") (pinfunction "1_1") (pintype "unspecified"))
      (node (ref "R12") (pin "2") (pinfunction "2_2") (pintype "input"))
    )
    (net (code "51") (name "Net-(J2-Pad2)") (class "Default")
      (node (ref "J2") (pin "2") (pinfunction "2_2") (pintype "unspecified"))
      (node (ref "R13") (pin "2") (pinfunction "2_2") (pintype "input"))
    )
    (net (code "52") (name "Net-(J2-Pad3)") (class "Default")
      (node (ref "J2") (pin "3") (pinfunction "3_3") (pintype "unspecified"))
      (node (ref "R14") (pin "2") (pinfunction "2_2") (pintype "input"))
    )
    (net (code "53") (name "Net-(J2-Pad4)") (class "Default")
      (node (ref "J2") (pin "4") (pinfunction "4_4") (pintype "unspecified"))
      (node (ref "R15") (pin "2") (pinfunction "2_2") (pintype "input"))
    )
    (net (code "54") (name "Net-(J2-Pad5)") (class "Default")
      (node (ref "J2") (pin "5") (pinfunction "5_5") (pintype "unspecified"))
      (node (ref "R16") (pin "2") (pinfunction "2_2") (pintype "input"))
    )
    (net (code "55") (name "Net-(J2-Pad6)") (class "Default")
      (node (ref "J2") (pin "6") (pinfunction "6_6") (pintype "unspecified"))
      (node (ref "R17") (pin "2") (pinfunction "2_2") (pintype "input"))
    )
    (net (code "56") (name "Net-(J2-Pad7)") (class "Default")
      (node (ref "J2") (pin "7") (pinfunction "7_7") (pintype "unspecified"))
      (node (ref "R18") (pin "2") (pinfunction "2_2") (pintype "input"))
    )
    (net (code "57") (name "Net-(J2-Pad8)") (class "Default")
      (node (ref "J2") (pin "8") (pinfunction "8_8") (pintype "unspecified"))
      (node (ref "R19") (pin "2") (pinfunction "2_2") (pintype "input"))
    )
    (net (code "58") (name "Net-(J2-Pad9)") (class "Default")
      (node (ref "J2") (pin "9") (pinfunction "9_9") (pintype "unspecified"))
      (node (ref "R20") (pin "2") (pinfunction "2_2") (pintype "input"))
    )
    (net (code "59") (name "Net-(J2-Pad10)") (class "Default")
      (node (ref "J2") (pin "10") (pinfunction "10_10") (pintype "unspecified"))
      (node (ref "R21") (pin "2") (pinfunction "2_2") (pintype "input"))
    )
    (net (code "60") (name "Net-(J2-Pad11)") (class "Default")
      (node (ref "J2") (pin "11") (pinfunction "11_11") (pintype "unspecified"))
      (node (ref "R22") (pin "2") (pinfunction "2_2") (pintype "input"))
    )
    (net (code "61") (name "Net-(J2-Pad12)") (class "Default")
      (node (ref "J2") (pin "12") (pinfunction "12_12") (pintype "unspecified"))
      (node (ref "R23") (pin "2") (pinfunction "2_2") (pintype "input"))
    )
    (net (code "62") (name "Net-(J2-Pad13)") (class "Default")
      (node (ref "J2") (pin "13") (pinfunction "13_13") (pintype "unspecified"))
      (node (ref "R24") (pin "2") (pinfunction "2_2") (pintype "input"))
    )
    (net (code "63") (name "unconnected-(IC1-IN1N-Pad15)") (class "Default")
      (node (ref "IC1") (pin "15") (pinfunction "IN1N_15") (pintype "unspecified"))
    )
    (net (code "64") (name "unconnected-(IC1-IN2N-Pad13)") (class "Default")
      (node (ref "IC1") (pin "13") (pinfunction "IN2N_13") (pintype "unspecified"))
    )
    (net (code "65") (name "unconnected-(IC1-IN3N-Pad11)") (class "Default")
      (node (ref "IC1") (pin "11") (pinfunction "IN3N_11") (pintype "unspecified"))
    )
    (net (code "66") (name "unconnected-(IC1-IN4N-Pad9)") (class "Default")
      (node (ref "IC1") (pin "9") (pinfunction "IN4N_9") (pintype "unspecified"))
    )
    (net (code "67") (name "unconnected-(IC1-IN5N-Pad7)") (class "Default")
      (node (ref "IC1") (pin "7") (pinfunction "IN5N_7") (pintype "unspecified"))
    )
    (net (code "68") (name "unconnected-(IC1-IN6N-Pad5)") (class "Default")
      (node (ref "IC1") (pin "5") (pinfunction "IN6N_5") (pintype "unspecified"))
    )
    (net (code "69") (name "unconnected-(IC1-IN7N-Pad3)") (class "Default")
      (node (ref "IC1") (pin "3") (pinfunction "IN7N_3") (pintype "unspecified"))
    )
    (net (code "70") (name "unconnected-(IC1-IN8N-Pad1)") (class "Default")
      (node (ref "IC1") (pin "1") (pinfunction "IN8N_1") (pintype "unspecified"))
    )
    (net (code "71") (name "unconnected-(IC1-NC-Pad27)") (class "Default")
      (node (ref "IC1") (pin "27") (pinfunction "NC_27") (pintype "unspecified"))
    )
    (net (code "72") (name "unconnected-(IC1-NC-Pad29)") (class "Default")
      (node (ref "IC1") (pin "29") (pinfunction "NC_29") (pintype "unspecified"))
    )
    (net (code "73") (name "unconnected-(IC1-RESERVED-Pad64)") (class "Default")
      (node (ref "IC1") (pin "64") (pinfunction "RESERVED_64") (pintype "unspecified"))
    )
    (net (code "74") (name "unconnected-(IC1-SRB2-Pad18)") (class "Default")
      (node (ref "IC1") (pin "18") (pinfunction "SRB2_18") (pintype "unspecified"))
    )
  )
)
